# Radio.net
KiCad netlist of a schematic drawn in Altium Designer
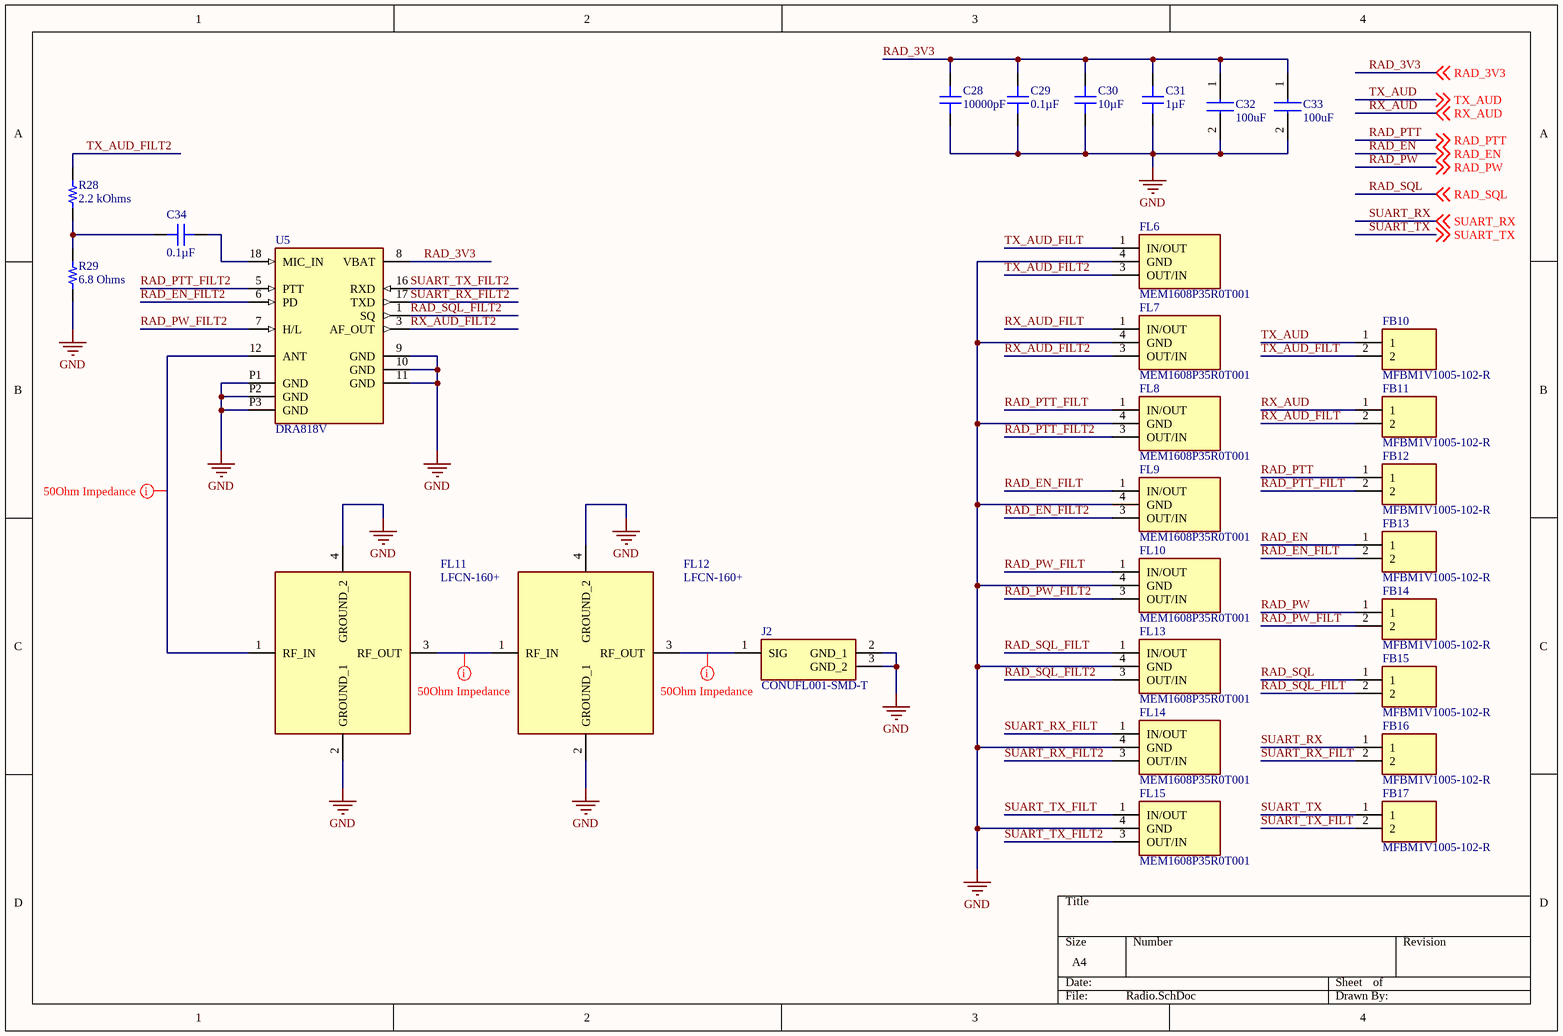
[diagram p0: Radio.SchDoc]

(export (version "E")
  (design (tool "Eeschema 10.0.6"))
  (components
    (comp (ref "C28")
      (value "10000pF")
      (footprint "CAP 0402_1005")
      (description "CAP CER 10000PF 50V X7R 0402")
      (fields
        (field (name "PART NUMBER") "0402B103K500CT")
        (field (name "MANUFACTURER") "Walsin Technology Corporation")
      )
      (libsource (lib "Celestial Altium Library - altium_library") (part "Capacitor"))
    )
    (comp (ref "C29")
      (value "0.1µF")
      (footprint "CAP 0402_1005")
      (description "CAP CER 0.1UF 6.3V X5R 0402")
      (fields (field (name "PART NUMBER") "C0402C104K9PACTU") (field (name "MANUFACTURER") "KEMET"))
      (libsource (lib "Celestial Altium Library - altium_library") (part "Capacitor"))
    )
    (comp (ref "C30")
      (value "10µF")
      (footprint "CAP 0402_1005")
      (description "CAP CER 10UF 6.3V X5R 0402")
      (fields (field (name "PART NUMBER") "C0402C106M9PAC7867") (field (name "MANUFACTURER") "KEMET"))
      (libsource (lib "Celestial Altium Library - altium_library") (part "Capacitor"))
    )
    (comp (ref "C31")
      (value "1µF")
      (footprint "CAP 0402_1005")
      (description "CAP CER 1UF 16V X5R 0402")
      (fields (field (name "PART NUMBER") "0402YD105KAT2A") (field (name "MANUFACTURER") "AVX Corporation"))
      (libsource (lib "Celestial Altium Library - altium_library") (part "Capacitor"))
    )
    (comp (ref "C32")
      (value "100uF")
      (footprint "SamacSys:CAPC3225X270N")
      (description "Capacitor")
      (fields
        (field (name "MOUSER2 PART NUMBER") "81-GRM32EC70J107ME5L")
        (field (name "MANUFACTURER_PART_NUMBER") "GRM32EC70J107ME15L")
      )
      (libsource (lib "*") (part "GRM32EC70J107ME15L"))
    )
    (comp (ref "C33")
      (value "100uF")
      (footprint "SamacSys:CAPC3225X270N")
      (description "Capacitor")
      (fields
        (field (name "MOUSER2 PART NUMBER") "81-GRM32EC70J107ME5L")
        (field (name "MANUFACTURER_PART_NUMBER") "GRM32EC70J107ME15L")
      )
      (libsource (lib "*") (part "GRM32EC70J107ME15L"))
    )
    (comp (ref "C34")
      (value "0.1µF")
      (footprint "CAP 0402_1005")
      (description "CAP CER 0.1UF 6.3V X5R 0402")
      (fields (field (name "PART NUMBER") "C0402C104K9PACTU") (field (name "MANUFACTURER") "KEMET"))
      (libsource (lib "Celestial Altium Library - altium_library") (part "Capacitor"))
    )
    (comp (ref "FB10")
      (value "MFBM1V1005-102-R")
      (footprint "SamacSys:BEADC1005X65N")
      (description "Ferrite Bead")
      (fields (field (name "MANUFACTURER_PART_NUMBER") "MFBM1V1005-101-R"))
      (libsource (lib "SamacSys") (part "MFBM1V1005-102-R"))
    )
    (comp (ref "FB11")
      (value "MFBM1V1005-102-R")
      (footprint "SamacSys:BEADC1005X65N")
      (description "Ferrite Bead")
      (fields (field (name "MANUFACTURER_PART_NUMBER") "MFBM1V1005-101-R"))
      (libsource (lib "SamacSys") (part "MFBM1V1005-102-R"))
    )
    (comp (ref "FB12")
      (value "MFBM1V1005-102-R")
      (footprint "SamacSys:BEADC1005X65N")
      (description "Ferrite Bead")
      (fields (field (name "MANUFACTURER_PART_NUMBER") "MFBM1V1005-101-R"))
      (libsource (lib "SamacSys") (part "MFBM1V1005-102-R"))
    )
    (comp (ref "FB13")
      (value "MFBM1V1005-102-R")
      (footprint "SamacSys:BEADC1005X65N")
      (description "Ferrite Bead")
      (fields (field (name "MANUFACTURER_PART_NUMBER") "MFBM1V1005-101-R"))
      (libsource (lib "SamacSys") (part "MFBM1V1005-102-R"))
    )
    (comp (ref "FB14")
      (value "MFBM1V1005-102-R")
      (footprint "SamacSys:BEADC1005X65N")
      (description "Ferrite Bead")
      (fields (field (name "MANUFACTURER_PART_NUMBER") "MFBM1V1005-101-R"))
      (libsource (lib "SamacSys") (part "MFBM1V1005-102-R"))
    )
    (comp (ref "FB15")
      (value "MFBM1V1005-102-R")
      (footprint "SamacSys:BEADC1005X65N")
      (description "Ferrite Bead")
      (fields (field (name "MANUFACTURER_PART_NUMBER") "MFBM1V1005-101-R"))
      (libsource (lib "SamacSys") (part "MFBM1V1005-102-R"))
    )
    (comp (ref "FB16")
      (value "MFBM1V1005-102-R")
      (footprint "SamacSys:BEADC1005X65N")
      (description "Ferrite Bead")
      (fields (field (name "MANUFACTURER_PART_NUMBER") "MFBM1V1005-101-R"))
      (libsource (lib "SamacSys") (part "MFBM1V1005-102-R"))
    )
    (comp (ref "FB17")
      (value "MFBM1V1005-102-R")
      (footprint "SamacSys:BEADC1005X65N")
      (description "Ferrite Bead")
      (fields (field (name "MANUFACTURER_PART_NUMBER") "MFBM1V1005-101-R"))
      (libsource (lib "SamacSys") (part "MFBM1V1005-102-R"))
    )
    (comp (ref "FL6")
      (value "MEM1608P35R0T001")
      (footprint "SamacSys:MEM1608P35R0T001")
      (description "Filter")
      (libsource (lib "SamacSys") (part "MEM1608P35R0T001"))
    )
    (comp (ref "FL7")
      (value "MEM1608P35R0T001")
      (footprint "SamacSys:MEM1608P35R0T001")
      (description "Filter")
      (libsource (lib "SamacSys") (part "MEM1608P35R0T001"))
    )
    (comp (ref "FL8")
      (value "MEM1608P35R0T001")
      (footprint "SamacSys:MEM1608P35R0T001")
      (description "Filter")
      (libsource (lib "SamacSys") (part "MEM1608P35R0T001"))
    )
    (comp (ref "FL9")
      (value "MEM1608P35R0T001")
      (footprint "SamacSys:MEM1608P35R0T001")
      (description "Filter")
      (libsource (lib "SamacSys") (part "MEM1608P35R0T001"))
    )
    (comp (ref "FL10")
      (value "MEM1608P35R0T001")
      (footprint "SamacSys:MEM1608P35R0T001")
      (description "Filter")
      (libsource (lib "SamacSys") (part "MEM1608P35R0T001"))
    )
    (comp (ref "FL11")
      (value "LFCN-160+")
      (footprint "SamacSys:LFCN160")
      (description "Filter")
      (libsource (lib "*") (part "LFCN-160+"))
    )
    (comp (ref "FL12")
      (value "LFCN-160+")
      (footprint "SamacSys:LFCN160")
      (description "Filter")
      (libsource (lib "*") (part "LFCN-160+"))
    )
    (comp (ref "FL13")
      (value "MEM1608P35R0T001")
      (footprint "SamacSys:MEM1608P35R0T001")
      (description "Filter")
      (libsource (lib "SamacSys") (part "MEM1608P35R0T001"))
    )
    (comp (ref "FL14")
      (value "MEM1608P35R0T001")
      (footprint "SamacSys:MEM1608P35R0T001")
      (description "Filter")
      (libsource (lib "SamacSys") (part "MEM1608P35R0T001"))
    )
    (comp (ref "FL15")
      (value "MEM1608P35R0T001")
      (footprint "SamacSys:MEM1608P35R0T001")
      (description "Filter")
      (libsource (lib "SamacSys") (part "MEM1608P35R0T001"))
    )
    (comp (ref "J2")
      (value "CONUFL001-SMD-T")
      (footprint "SamacSys:CONUFL001-SMD")
      (description "Connector")
      (fields (field (name "MOUSER2 PART NUMBER") "712-CONUFL001-SMD-T"))
      (libsource (lib "SamacSys") (part "CONUFL001-SMD-T"))
    )
    (comp (ref "R28")
      (value "2.2 kOhms")
      (footprint "RES 0402_1005")
      (description "RES SMD 2.2K OHM 0.1% 1/16W 0402")
      (fields
        (field (name "PART NUMBER") "CPF0402B2K2E1")
        (field (name "MANUFACTURER") "TE Connectivity Passive Product")
      )
      (libsource (lib "Celestial Altium Library - altium_library") (part "Resistor"))
    )
    (comp (ref "R29")
      (value "6.8 Ohms")
      (footprint "RES 0402_1005")
      (description "RES SMD 6.8 OHM 5% 1/10W 0402")
      (fields
        (field (name "PART NUMBER") "ERJ-2GEJ6R8X")
        (field (name "MANUFACTURER") "Panasonic Electronic Components")
      )
      (libsource (lib "Celestial Altium Library - altium_library") (part "Resistor"))
    )
    (comp (ref "U5")
      (value "DRA818V")
      (footprint "DORJI_DRA818V")
      (description "VHF Band Voice Transceiver Module")
      (fields (field (name "MF") "DORJI"))
      (libsource (lib "DRA818V") (part "DRA818V"))
    )
  )
  (nets
    (net (code "1") (name "/RAD_EN_FILT") (class "Default")
      (node (ref "FB13") (pin "2") (pinfunction "2_2") (pintype "passive"))
      (node (ref "FL9") (pin "1") (pinfunction "IN/OUT_1") (pintype "passive"))
    )
    (net (code "2") (name "/RAD_EN_FILT2") (class "Default")
      (node (ref "FL9") (pin "3") (pinfunction "OUT/IN_3") (pintype "passive"))
      (node (ref "U5") (pin "6") (pinfunction "PD_6") (pintype "input"))
    )
    (net (code "3") (name "/RAD_PTT_FILT") (class "Default")
      (node (ref "FB12") (pin "2") (pinfunction "2_2") (pintype "passive"))
      (node (ref "FL8") (pin "1") (pinfunction "IN/OUT_1") (pintype "passive"))
    )
    (net (code "4") (name "/RAD_PTT_FILT2") (class "Default")
      (node (ref "FL8") (pin "3") (pinfunction "OUT/IN_3") (pintype "passive"))
      (node (ref "U5") (pin "5") (pinfunction "PTT_5") (pintype "input"))
    )
    (net (code "5") (name "/RAD_PW_FILT") (class "Default")
      (node (ref "FB14") (pin "2") (pinfunction "2_2") (pintype "passive"))
      (node (ref "FL10") (pin "1") (pinfunction "IN/OUT_1") (pintype "passive"))
    )
    (net (code "6") (name "/RAD_PW_FILT2") (class "Default")
      (node (ref "FL10") (pin "3") (pinfunction "OUT/IN_3") (pintype "passive"))
      (node (ref "U5") (pin "7") (pinfunction "H/L_7") (pintype "input"))
    )
    (net (code "7") (name "/RAD_SQL_FILT") (class "Default")
      (node (ref "FB15") (pin "2") (pinfunction "2_2") (pintype "passive"))
      (node (ref "FL13") (pin "1") (pinfunction "IN/OUT_1") (pintype "passive"))
    )
    (net (code "8") (name "/RAD_SQL_FILT2") (class "Default")
      (node (ref "FL13") (pin "3") (pinfunction "OUT/IN_3") (pintype "passive"))
      (node (ref "U5") (pin "1") (pinfunction "SQ_1") (pintype "output"))
    )
    (net (code "9") (name "/RX_AUD_FILT") (class "Default")
      (node (ref "FB11") (pin "2") (pinfunction "2_2") (pintype "passive"))
      (node (ref "FL7") (pin "1") (pinfunction "IN/OUT_1") (pintype "passive"))
    )
    (net (code "10") (name "/RX_AUD_FILT2") (class "Default")
      (node (ref "FL7") (pin "3") (pinfunction "OUT/IN_3") (pintype "passive"))
      (node (ref "U5") (pin "3") (pinfunction "AF_OUT_3") (pintype "output"))
    )
    (net (code "11") (name "/SUART_RX_FILT") (class "Default")
      (node (ref "FB16") (pin "2") (pinfunction "2_2") (pintype "passive"))
      (node (ref "FL14") (pin "1") (pinfunction "IN/OUT_1") (pintype "passive"))
    )
    (net (code "12") (name "/SUART_RX_FILT2") (class "Default")
      (node (ref "FL14") (pin "3") (pinfunction "OUT/IN_3") (pintype "passive"))
      (node (ref "U5") (pin "17") (pinfunction "TXD_17") (pintype "output"))
    )
    (net (code "13") (name "/SUART_TX_FILT") (class "Default")
      (node (ref "FB17") (pin "2") (pinfunction "2_2") (pintype "passive"))
      (node (ref "FL15") (pin "1") (pinfunction "IN/OUT_1") (pintype "passive"))
    )
    (net (code "14") (name "/SUART_TX_FILT2") (class "Default")
      (node (ref "FL15") (pin "3") (pinfunction "OUT/IN_3") (pintype "passive"))
      (node (ref "U5") (pin "16") (pinfunction "RXD_16") (pintype "input"))
    )
    (net (code "15") (name "/TX_AUD_FILT") (class "Default")
      (node (ref "FB10") (pin "2") (pinfunction "2_2") (pintype "passive"))
      (node (ref "FL6") (pin "1") (pinfunction "IN/OUT_1") (pintype "passive"))
    )
    (net (code "16") (name "/TX_AUD_FILT2") (class "Default")
      (node (ref "FL6") (pin "3") (pinfunction "OUT/IN_3") (pintype "passive"))
      (node (ref "R28") (pin "1") (pinfunction "1_1") (pintype "passive"))
    )
    (net (code "17") (name "GND") (class "Default")
      (node (ref "C28") (pin "1") (pinfunction "1_1") (pintype "passive"))
      (node (ref "C29") (pin "1") (pinfunction "1_1") (pintype "passive"))
      (node (ref "C30") (pin "1") (pinfunction "1_1") (pintype "passive"))
      (node (ref "C31") (pin "1") (pinfunction "1_1") (pintype "passive"))
      (node (ref "C32") (pin "2") (pinfunction "2_2") (pintype "passive"))
      (node (ref "C33") (pin "2") (pinfunction "2_2") (pintype "passive"))
      (node (ref "FL10") (pin "4") (pinfunction "GND_4") (pintype "passive"))
      (node (ref "FL11") (pin "2") (pinfunction "GROUND_1_2") (pintype "passive"))
      (node (ref "FL11") (pin "4") (pinfunction "GROUND_2_4") (pintype "passive"))
      (node (ref "FL12") (pin "2") (pinfunction "GROUND_1_2") (pintype "passive"))
      (node (ref "FL12") (pin "4") (pinfunction "GROUND_2_4") (pintype "passive"))
      (node (ref "FL13") (pin "4") (pinfunction "GND_4") (pintype "passive"))
      (node (ref "FL14") (pin "4") (pinfunction "GND_4") (pintype "passive"))
      (node (ref "FL15") (pin "4") (pinfunction "GND_4") (pintype "passive"))
      (node (ref "FL6") (pin "4") (pinfunction "GND_4") (pintype "passive"))
      (node (ref "FL7") (pin "4") (pinfunction "GND_4") (pintype "passive"))
      (node (ref "FL8") (pin "4") (pinfunction "GND_4") (pintype "passive"))
      (node (ref "FL9") (pin "4") (pinfunction "GND_4") (pintype "passive"))
      (node (ref "J2") (pin "2") (pinfunction "GND_1_2") (pintype "passive"))
      (node (ref "J2") (pin "3") (pinfunction "GND_2_3") (pintype "passive"))
      (node (ref "R29") (pin "1") (pinfunction "1_1") (pintype "passive"))
      (node (ref "U5") (pin "10") (pinfunction "GND_10") (pintype "power_in"))
      (node (ref "U5") (pin "11") (pinfunction "GND_11") (pintype "power_in"))
      (node (ref "U5") (pin "9") (pinfunction "GND_9") (pintype "power_in"))
      (node (ref "U5") (pin "P1") (pinfunction "GND_P1") (pintype "power_in"))
      (node (ref "U5") (pin "P2") (pinfunction "GND_P2") (pintype "power_in"))
      (node (ref "U5") (pin "P3") (pinfunction "GND_P3") (pintype "power_in"))
    )
    (net (code "18") (name "Net-(C34-Pad2)") (class "Default")
      (node (ref "C34") (pin "2") (pinfunction "2_2") (pintype "passive"))
      (node (ref "R28") (pin "2") (pinfunction "2_2") (pintype "passive"))
      (node (ref "R29") (pin "2") (pinfunction "2_2") (pintype "passive"))
    )
    (net (code "19") (name "Net-(FL11-RF_IN)") (class "Default")
      (node (ref "FL11") (pin "1") (pinfunction "RF_IN_1") (pintype "passive"))
      (node (ref "U5") (pin "12") (pinfunction "ANT_12") (pintype "passive"))
    )
    (net (code "20") (name "Net-(FL11-RF_OUT)") (class "Default")
      (node (ref "FL11") (pin "3") (pinfunction "RF_OUT_3") (pintype "passive"))
      (node (ref "FL12") (pin "1") (pinfunction "RF_IN_1") (pintype "passive"))
    )
    (net (code "21") (name "Net-(FL12-RF_OUT)") (class "Default")
      (node (ref "FL12") (pin "3") (pinfunction "RF_OUT_3") (pintype "passive"))
      (node (ref "J2") (pin "1") (pinfunction "SIG_1") (pintype "passive"))
    )
    (net (code "22") (name "Net-(U5-MIC_IN)") (class "Default")
      (node (ref "C34") (pin "1") (pinfunction "1_1") (pintype "passive"))
      (node (ref "U5") (pin "18") (pinfunction "MIC_IN_18") (pintype "input"))
    )
    (net (code "23") (name "RAD_3V3") (class "Default")
      (node (ref "C28") (pin "2") (pinfunction "2_2") (pintype "passive"))
      (node (ref "C29") (pin "2") (pinfunction "2_2") (pintype "passive"))
      (node (ref "C30") (pin "2") (pinfunction "2_2") (pintype "passive"))
      (node (ref "C31") (pin "2") (pinfunction "2_2") (pintype "passive"))
      (node (ref "C32") (pin "1") (pinfunction "1_1") (pintype "passive"))
      (node (ref "C33") (pin "1") (pinfunction "1_1") (pintype "passive"))
      (node (ref "U5") (pin "8") (pinfunction "VBAT_8") (pintype "power_in"))
    )
    (net (code "24") (name "RAD_EN") (class "Default")
      (node (ref "FB13") (pin "1") (pinfunction "1_1") (pintype "passive"))
    )
    (net (code "25") (name "RAD_PTT") (class "Default")
      (node (ref "FB12") (pin "1") (pinfunction "1_1") (pintype "passive"))
    )
    (net (code "26") (name "RAD_PW") (class "Default")
      (node (ref "FB14") (pin "1") (pinfunction "1_1") (pintype "passive"))
    )
    (net (code "27") (name "RAD_SQL") (class "Default")
      (node (ref "FB15") (pin "1") (pinfunction "1_1") (pintype "passive"))
    )
    (net (code "28") (name "RX_AUD") (class "Default")
      (node (ref "FB11") (pin "1") (pinfunction "1_1") (pintype "passive"))
    )
    (net (code "29") (name "SUART_RX") (class "Default")
      (node (ref "FB16") (pin "1") (pinfunction "1_1") (pintype "passive"))
    )
    (net (code "30") (name "SUART_TX") (class "Default")
      (node (ref "FB17") (pin "1") (pinfunction "1_1") (pintype "passive"))
    )
    (net (code "31") (name "TX_AUD") (class "Default")
      (node (ref "FB10") (pin "1") (pinfunction "1_1") (pintype "passive"))
    )
  )
)
